# SH1_-_POWER_CAN_LED.net
KiCad netlist of a schematic drawn in Altium Designer
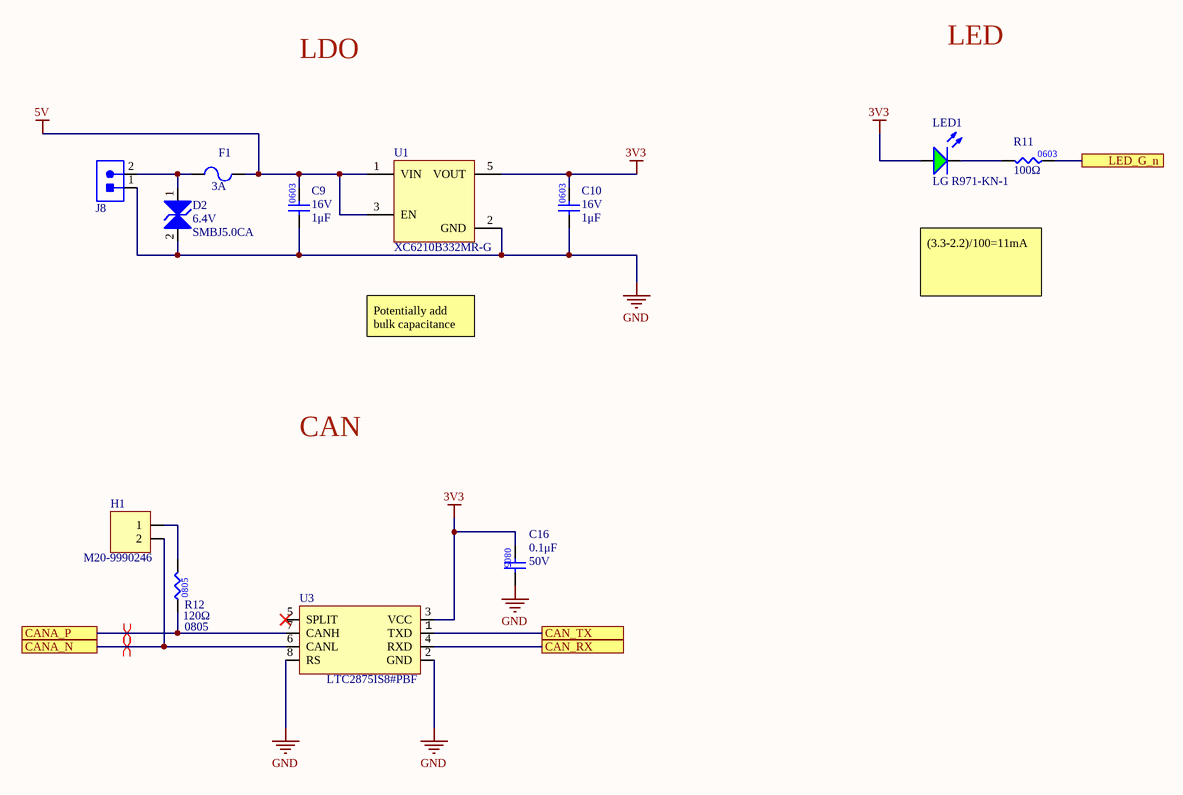
[diagram p0: SH1 - POWER, CAN, LED.SchDoc]

(export (version "E")
  (design (tool "Eeschema 10.0.6"))
  (components
    (comp (ref "C9")
      (value "1μF")
      (footprint "CAP0603")
      (description "CAP CER 1UF 16V Y5V 0603")
      (fields (field (name "VOLTAGE RATING") "16V") (field (name "Comment") "CAP_1uF_16V_0603"))
      (libsource (lib "UWRT_Schematic_Library_2020") (part "CAP_1uF_16V_0603"))
    )
    (comp (ref "C10")
      (value "1μF")
      (footprint "CAP0603")
      (description "CAP CER 1UF 16V Y5V 0603")
      (fields (field (name "VOLTAGE RATING") "16V") (field (name "Comment") "CAP_1uF_16V_0603"))
      (libsource (lib "UWRT_Schematic_Library_2020") (part "CAP_1uF_16V_0603"))
    )
    (comp (ref "C16")
      (value "0.1μF")
      (footprint "CAP0805")
      (description "CAP CER 0.1UF 50V X7R 0805")
      (fields
        (field (name "VOLTAGE RATING") "50V")
        (field (name "LCSC PART #") "C49678")
        (field (name "Comment") "CAP_0.1uF_50V_0805")
      )
      (libsource (lib "UWRT_Schematic_Library_2020") (part "CAP_0.1uF_50V_0805"))
    )
    (comp (ref "D2")
      (value "TVS_DIODE_BIDIR_5V")
      (footprint "TVS_DIODE_BIDIR_SMB")
      (description "TVS DIODE 5V 9.2V SMB")
      (fields
        (field (name "VOLTAGE - BREAKDOWN (MIN)") "6.4V")
        (field (name "MANUFACTURER PART NUMBER 1") "SMBJ5.0CA")
      )
      (libsource (lib "UWRT_Schematic_Library_2020") (part "TVS_DIODE_BIDIR_5V"))
    )
    (comp (ref "F1")
      (value "FUSE_3A_0603")
      (footprint "FUSE_0603")
      (description "FUSE SMD 3A 32V 0603")
      (libsource (lib "UWRT_Schematic_Library_2020") (part "FUSE_3A_0603"))
    )
    (comp (ref "H1")
      (value "JUMPER")
      (footprint "HDR1X2")
      (description "HEADER 2X1")
      (fields (field (name "MANUFACTURER PART NUMBER 1") "M20-9990246"))
      (libsource (lib "UWRT_Schematic_Library_2020") (part "JUMPER"))
    )
    (comp (ref "J8")
      (value "CON_2POS_SCREW_TERM")
      (footprint "1935161")
      (description "TERM BLK 2POS SIDE ENTRY 5MM")
      (libsource (lib "UWRT_Schematic_Library_2020") (part "CON_2POS_SCREW_TERM"))
    )
    (comp (ref "LED1")
      (value "LED_GREEN")
      (footprint "LED_0805_GREEN")
      (description "LED GREEN DIFFUSED 0805 SMD")
      (fields (field (name "MANUFACTURER PART NUMBER 1") "LG R971-KN-1"))
      (libsource (lib "UWRT_Schematic_Library_2020") (part "LED_GREEN"))
    )
    (comp (ref "R11")
      (value "100Ω")
      (footprint "RES0603")
      (description "RES 100 OHM 1% 1/10W 0603")
      (fields (field (name "Comment") "RES_100Ω_0603_1%"))
      (libsource (lib "UWRT_Schematic_Library_2020") (part "RES_100Ω_0603_1%"))
    )
    (comp (ref "R12")
      (value "120Ω")
      (footprint "RES0805")
      (description "RES 120 OHM 1% 1/8W 0805")
      (fields
        (field (name "LCSC PART #") "C17437")
        (field (name "PACKAGE/FOOTPRINT") "0805")
        (field (name "Comment") "RES_120Ω_0805_1%")
      )
      (libsource (lib "UWRT_Schematic_Library_2020") (part "RES_120Ω_0805_1%"))
    )
    (comp (ref "U1")
      (value "LDO_3.3V_700mA")
      (footprint "SOT95P285X140-5N")
      (description "IC REG LINEAR 3.3V 700MA SOT25")
      (fields (field (name "MANUFACTURER PART NUMBER 1") "XC6210B332MR-G"))
      (libsource (lib "UWRT_Schematic_Library_2020") (part "LDO_3.3V_700mA"))
    )
    (comp (ref "U3")
      (value "IC_CAN_TRANSCEIVER")
      (footprint "LT-S8_N")
      (description "IC TXRX CAN 4MBPS 8SO")
      (fields
        (field (name "MANUFACTURER PART NUMBER 1") "LTC2875IS8#PBF")
        (field (name "LCSC PART #") "C117076")
      )
      (libsource (lib "UWRT_Schematic_Library_2020") (part "IC_CAN_TRANSCEIVER"))
    )
  )
  (nets
    (net (code "1") (name "/CANA_N") (class "Default")
      (node (ref "H1") (pin "2") (pinfunction "2_2") (pintype "passive"))
      (node (ref "U3") (pin "6") (pinfunction "CANL_6") (pintype "passive"))
    )
    (net (code "2") (name "/CANA_P") (class "Default")
      (node (ref "R12") (pin "1") (pinfunction "1_1") (pintype "passive"))
      (node (ref "U3") (pin "7") (pinfunction "CANH_7") (pintype "passive"))
    )
    (net (code "3") (name "/CAN_RX") (class "Default")
      (node (ref "U3") (pin "4") (pinfunction "RXD_4") (pintype "passive"))
    )
    (net (code "4") (name "/CAN_TX") (class "Default")
      (node (ref "U3") (pin "1") (pinfunction "TXD_1") (pintype "passive"))
    )
    (net (code "5") (name "/LED_G_n") (class "Default")
      (node (ref "R11") (pin "2") (pinfunction "2_2") (pintype "passive"))
    )
    (net (code "6") (name "3V3") (class "Default")
      (node (ref "C10") (pin "2") (pinfunction "2_2") (pintype "passive"))
      (node (ref "C16") (pin "1") (pinfunction "1_1") (pintype "passive"))
      (node (ref "LED1") (pin "1") (pinfunction "A_1") (pintype "passive"))
      (node (ref "U1") (pin "5") (pinfunction "VOUT_5") (pintype "passive"))
      (node (ref "U3") (pin "3") (pinfunction "VCC_3") (pintype "passive"))
    )
    (net (code "7") (name "5V") (class "Default")
      (node (ref "C9") (pin "2") (pinfunction "2_2") (pintype "passive"))
      (node (ref "F1") (pin "2") (pinfunction "2_2") (pintype "passive"))
      (node (ref "U1") (pin "1") (pinfunction "VIN_1") (pintype "passive"))
      (node (ref "U1") (pin "3") (pinfunction "EN_3") (pintype "passive"))
    )
    (net (code "8") (name "GND") (class "Default")
      (node (ref "C10") (pin "1") (pinfunction "1_1") (pintype "passive"))
      (node (ref "C16") (pin "2") (pinfunction "2_2") (pintype "passive"))
      (node (ref "C9") (pin "1") (pinfunction "1_1") (pintype "passive"))
      (node (ref "D2") (pin "2") (pinfunction "2_2") (pintype "passive"))
      (node (ref "J8") (pin "1") (pinfunction "1_1") (pintype "passive"))
      (node (ref "U1") (pin "2") (pinfunction "GND_2") (pintype "passive"))
      (node (ref "U3") (pin "2") (pinfunction "GND_2") (pintype "passive"))
      (node (ref "U3") (pin "8") (pinfunction "RS_8") (pintype "passive"))
    )
    (net (code "9") (name "Net-(D2-Pad1)") (class "Default")
      (node (ref "D2") (pin "1") (pinfunction "1_1") (pintype "passive"))
      (node (ref "F1") (pin "1") (pinfunction "1_1") (pintype "passive"))
      (node (ref "J8") (pin "2") (pinfunction "2_2") (pintype "passive"))
    )
    (net (code "10") (name "Net-(H1-Pad1)") (class "Default")
      (node (ref "H1") (pin "1") (pinfunction "1_1") (pintype "passive"))
      (node (ref "R12") (pin "2") (pinfunction "2_2") (pintype "passive"))
    )
    (net (code "11") (name "Net-(LED1-K)") (class "Default")
      (node (ref "LED1") (pin "2") (pinfunction "K_2") (pintype "passive"))
      (node (ref "R11") (pin "1") (pinfunction "1_1") (pintype "passive"))
    )
    (net (code "12") (name "unconnected-(U3-SPLIT-Pad5)") (class "Default")
      (node (ref "U3") (pin "5") (pinfunction "SPLIT_5") (pintype "passive+no_connect"))
    )
  )
)
